# db9_trs_adapter.net
KiCad netlist of a schematic drawn in EAGLE
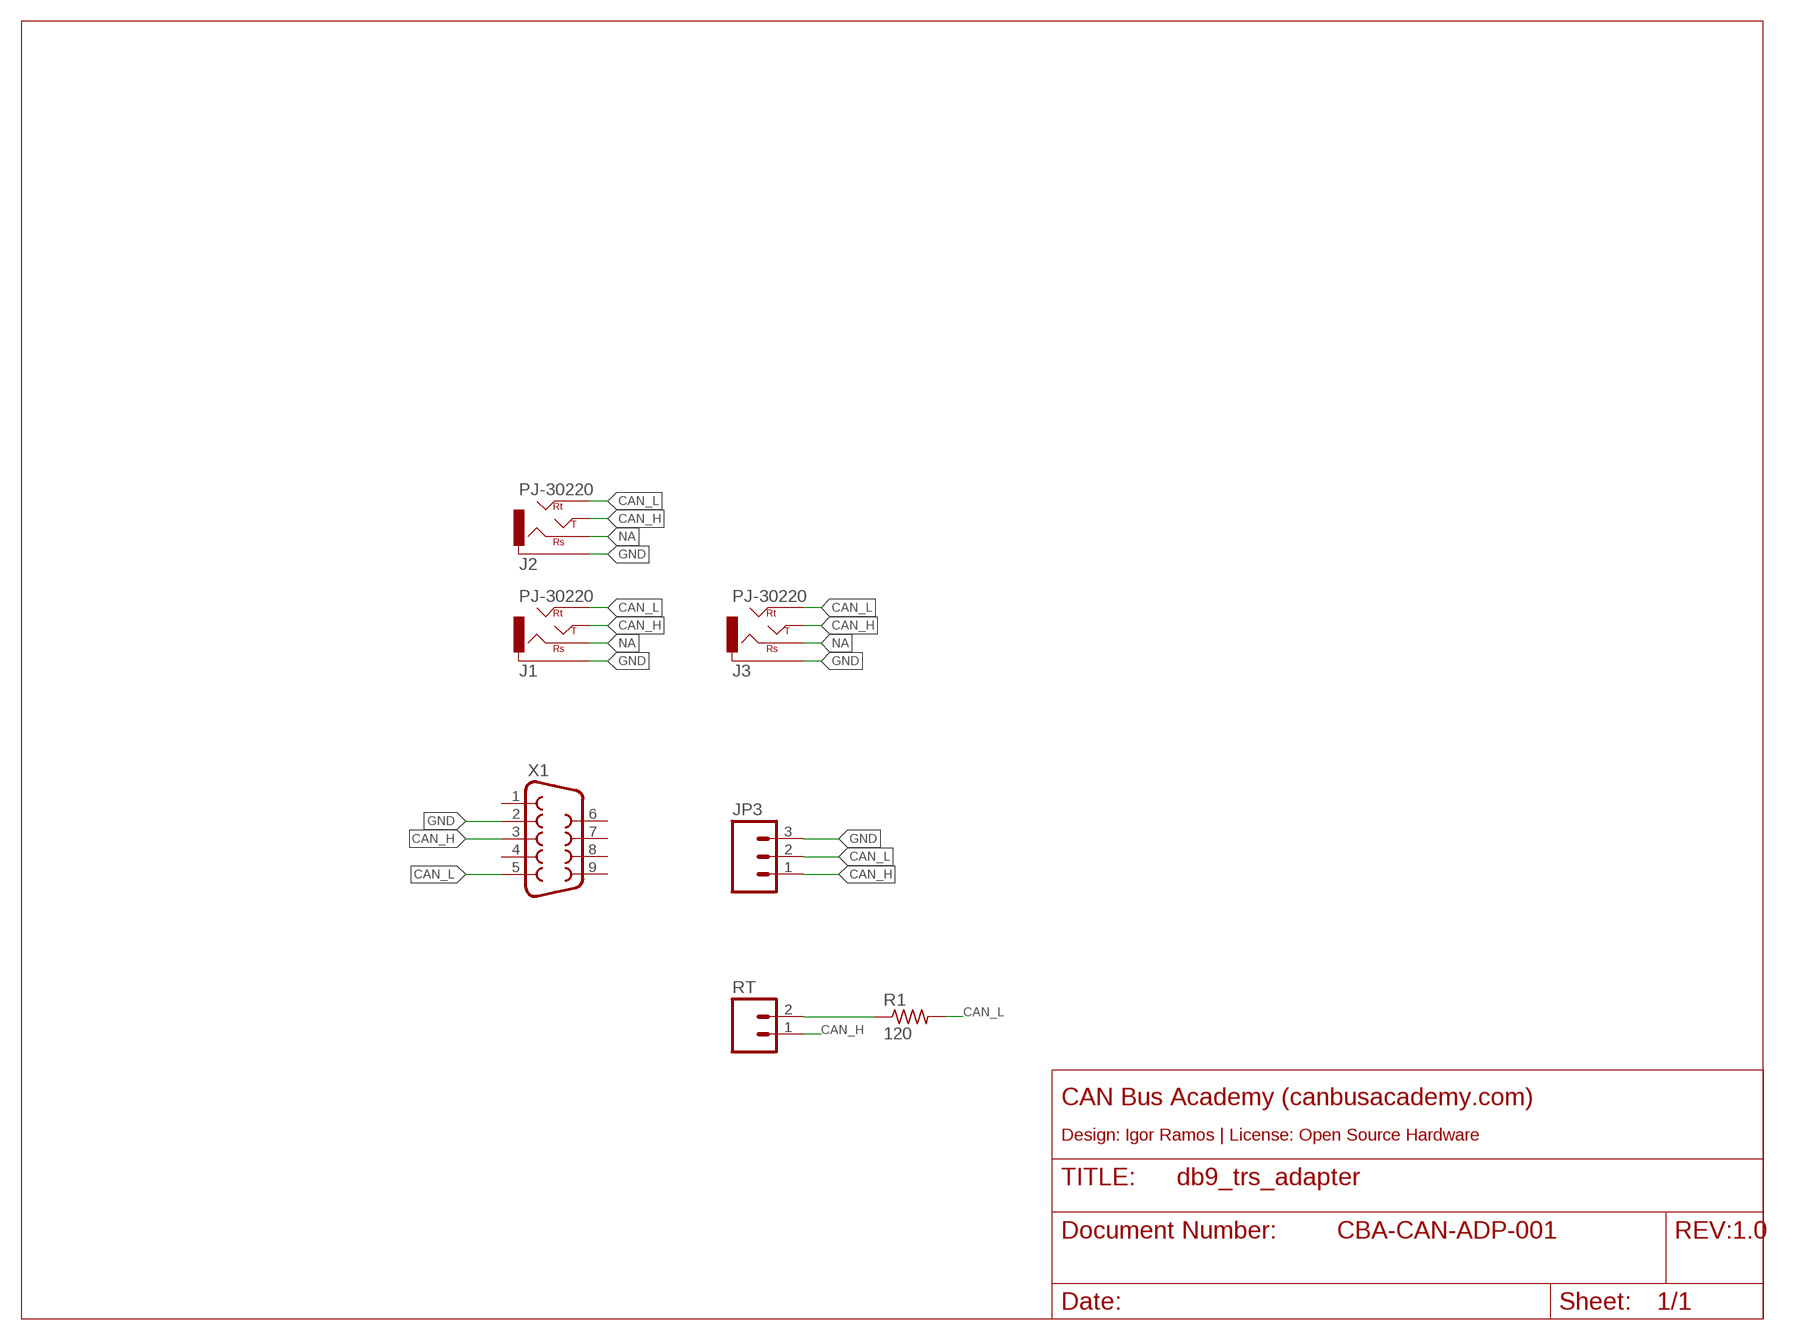
[diagram p0: schematic, sheet 1]

(export (version "E")
  (design (tool "Eeschema 10.0.6"))
  (components
    (comp (ref "J1")
      (value "PJ-30220")
      (footprint "eagle-import:PJ-30220")
      (fields (field (name "PARTNO") "PJ30220"))
      (libsource (lib "eagle-import") (part "AUDIO_JACK_4POSA"))
    )
    (comp (ref "J2")
      (value "PJ-30220")
      (footprint "eagle-import:PJ-30220")
      (fields (field (name "PARTNO") "PJ30220"))
      (libsource (lib "eagle-import") (part "AUDIO_JACK_4POSA"))
    )
    (comp (ref "J3")
      (value "PJ-30220")
      (footprint "eagle-import:PJ-30220")
      (fields (field (name "PARTNO") "PJ30220"))
      (libsource (lib "eagle-import") (part "AUDIO_JACK_4POSA"))
    )
    (comp (ref "JP3")
      (value "M03PTH")
      (footprint "eagle-import:1X03")
      (libsource (lib "eagle-import") (part "M03PTH"))
    )
    (comp (ref "R1")
      (value "120")
      (footprint "eagle-import:M0805")
      (libsource (lib "eagle-import") (part "R-US_M0805"))
    )
    (comp (ref "RT")
      (value "M02PTH")
      (footprint "eagle-import:1X02")
      (libsource (lib "eagle-import") (part "M02PTH"))
    )
    (comp (ref "X1")
      (value "DB9FEMALE")
      (footprint "eagle-import:DB9")
      (libsource (lib "eagle-import") (part "DB9FEMALE"))
    )
  )
  (nets
    (net (code "1") (name "CAN_H") (class "Default")
      (node (ref "J1") (pin "P$03") (pinfunction "TIP_P$03") (pintype "bidirectional"))
      (node (ref "J1") (pin "P$03B") (pinfunction "TIP_P$03B") (pintype "bidirectional"))
      (node (ref "J2") (pin "P$03") (pinfunction "TIP_P$03") (pintype "bidirectional"))
      (node (ref "J2") (pin "P$03B") (pinfunction "TIP_P$03B") (pintype "bidirectional"))
      (node (ref "J3") (pin "P$03") (pinfunction "TIP_P$03") (pintype "bidirectional"))
      (node (ref "J3") (pin "P$03B") (pinfunction "TIP_P$03B") (pintype "bidirectional"))
      (node (ref "JP3") (pin "1") (pinfunction "1_1") (pintype "passive"))
      (node (ref "RT") (pin "1") (pinfunction "1_1") (pintype "passive"))
      (node (ref "X1") (pin "3") (pinfunction "3_3") (pintype "passive"))
    )
    (net (code "2") (name "CAN_L") (class "Default")
      (node (ref "J1") (pin "P$04") (pinfunction "RT_P$04") (pintype "bidirectional"))
      (node (ref "J2") (pin "P$04") (pinfunction "RT_P$04") (pintype "bidirectional"))
      (node (ref "J3") (pin "P$04") (pinfunction "RT_P$04") (pintype "bidirectional"))
      (node (ref "JP3") (pin "2") (pinfunction "2_2") (pintype "passive"))
      (node (ref "R1") (pin "2") (pinfunction "2_2") (pintype "passive"))
      (node (ref "X1") (pin "5") (pinfunction "5_5") (pintype "passive"))
    )
    (net (code "3") (name "GND") (class "Default")
      (node (ref "J1") (pin "P$01") (pinfunction "SLEEVE_P$01") (pintype "bidirectional"))
      (node (ref "J2") (pin "P$01") (pinfunction "SLEEVE_P$01") (pintype "bidirectional"))
      (node (ref "J3") (pin "P$01") (pinfunction "SLEEVE_P$01") (pintype "bidirectional"))
      (node (ref "JP3") (pin "3") (pinfunction "3_3") (pintype "passive"))
      (node (ref "X1") (pin "2") (pinfunction "2_2") (pintype "passive"))
    )
    (net (code "4") (name "NA") (class "Default")
      (node (ref "J1") (pin "P$02") (pinfunction "RS_P$02") (pintype "bidirectional"))
      (node (ref "J2") (pin "P$02") (pinfunction "RS_P$02") (pintype "bidirectional"))
      (node (ref "J3") (pin "P$02") (pinfunction "RS_P$02") (pintype "bidirectional"))
    )
    (net (code "5") (name "Net-(R1-Pad1)") (class "Default")
      (node (ref "R1") (pin "1") (pinfunction "1_1") (pintype "passive"))
      (node (ref "RT") (pin "2") (pinfunction "2_2") (pintype "passive"))
    )
    (net (code "6") (name "unconnected-(X1-Pad1)") (class "Default")
      (node (ref "X1") (pin "1") (pinfunction "1_1") (pintype "passive"))
    )
    (net (code "7") (name "unconnected-(X1-Pad4)") (class "Default")
      (node (ref "X1") (pin "4") (pinfunction "4_4") (pintype "passive"))
    )
    (net (code "8") (name "unconnected-(X1-Pad6)") (class "Default")
      (node (ref "X1") (pin "6") (pinfunction "6_6") (pintype "passive"))
    )
    (net (code "9") (name "unconnected-(X1-Pad7)") (class "Default")
      (node (ref "X1") (pin "7") (pinfunction "7_7") (pintype "passive"))
    )
    (net (code "10") (name "unconnected-(X1-Pad8)") (class "Default")
      (node (ref "X1") (pin "8") (pinfunction "8_8") (pintype "passive"))
    )
    (net (code "11") (name "unconnected-(X1-Pad9)") (class "Default")
      (node (ref "X1") (pin "9") (pinfunction "9_9") (pintype "passive"))
    )
  )
)
